# systematic.net
KiCad netlist of a schematic drawn in Altium Designer
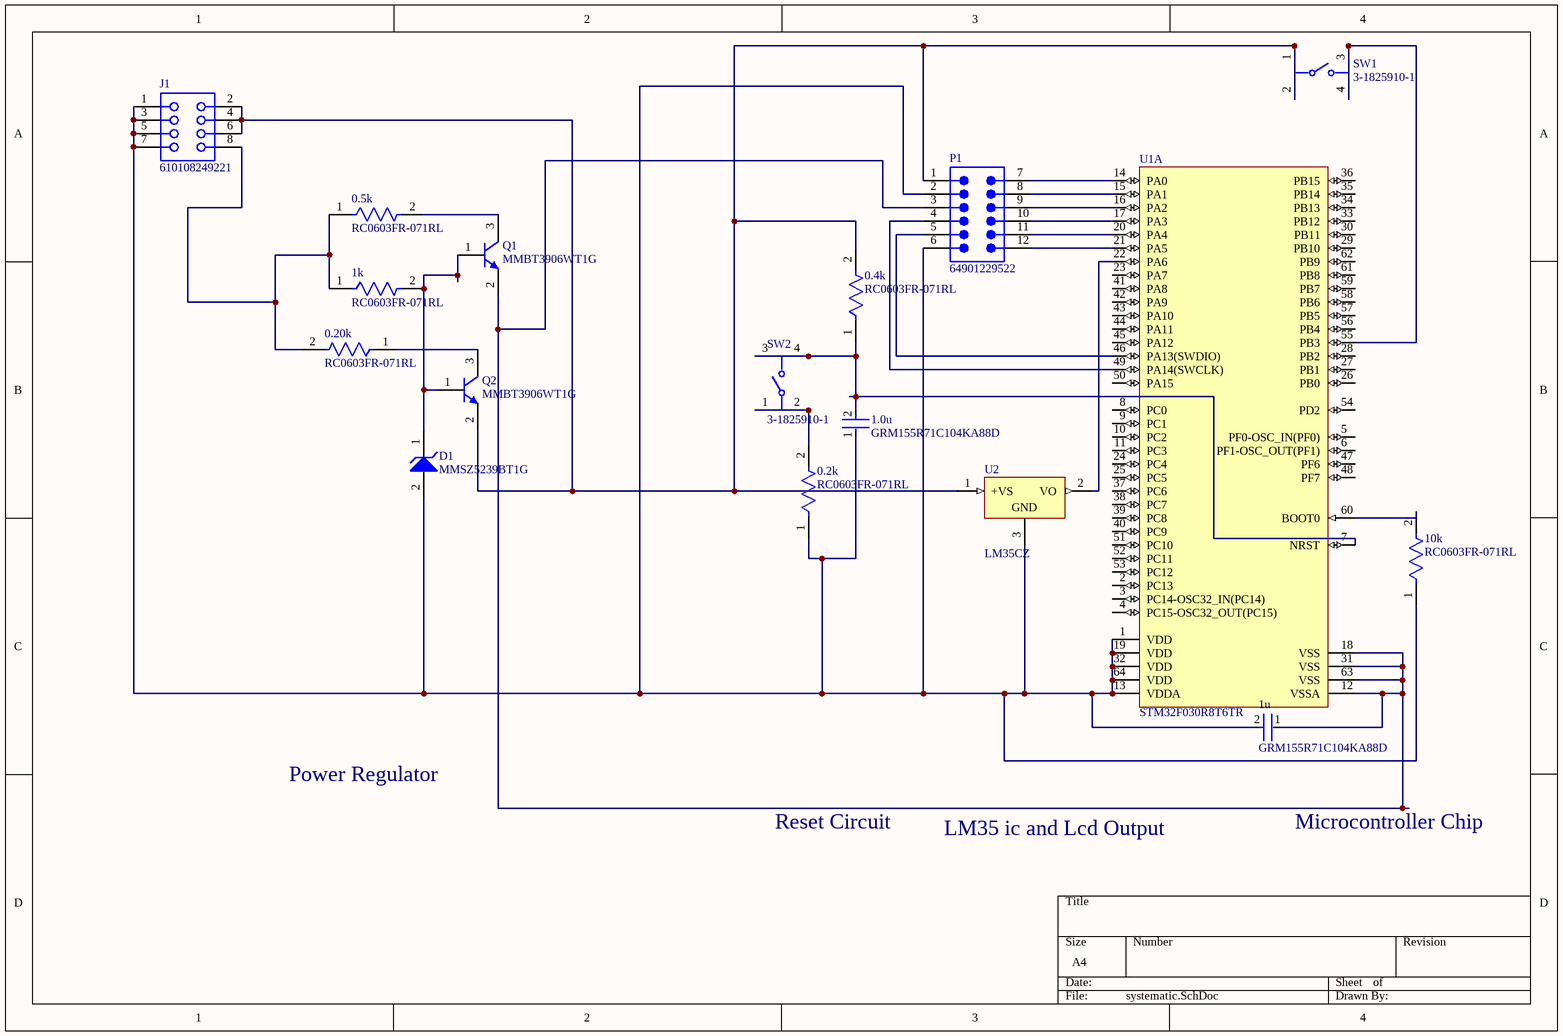
[diagram p0: systematic.SchDoc]

(export (version "E")
  (design (tool "Eeschema 10.0.6"))
  (components
    (comp (ref "0.2k")
      (value "RC0603FR-071RL")
      (footprint "FP-RC0603-0_55-MFG")
      (fields (field (name "TOLERANCE") "1%"))
      (libsource (lib "Altium Content Vault") (part "1029c3af85768c4190bb7ad29bc67b5"))
    )
    (comp (ref "0.4k")
      (value "RC0603FR-071RL")
      (footprint "FP-RC0603-0_55-MFG")
      (fields (field (name "TOLERANCE") "1%"))
      (libsource (lib "Altium Content Vault") (part "1029c3af85768c4190bb7ad29bc67b5"))
    )
    (comp (ref "0.5k")
      (value "RC0603FR-071RL")
      (footprint "FP-RC0603-0_55-MFG")
      (fields (field (name "TOLERANCE") "1%"))
      (libsource (lib "Altium Content Vault") (part "1029c3af85768c4190bb7ad29bc67b5"))
    )
    (comp (ref "0.20k")
      (value "RC0603FR-071RL")
      (footprint "FP-RC0603-0_55-MFG")
      (fields (field (name "TOLERANCE") "1%"))
      (libsource (lib "Altium Content Vault") (part "1029c3af85768c4190bb7ad29bc67b5"))
    )
    (comp (ref "1.0u")
      (value "GRM155R71C104KA88D")
      (footprint "FP-GRM15-MFG")
      (description "CAP CER 0.1UF 16V X7R 0402")
      (fields
        (field (name "TOLERANCE") "10%")
        (field (name "OCTOPART") "https://octopart.com/grm155r71c104ka88d-murata-196880")
      )
      (libsource (lib "Altium Content Vault") (part "236180d848d6139a670b325ea6854c9"))
    )
    (comp (ref "1k")
      (value "RC0603FR-071RL")
      (footprint "FP-RC0603-0_55-MFG")
      (fields (field (name "TOLERANCE") "1%"))
      (libsource (lib "Altium Content Vault") (part "1029c3af85768c4190bb7ad29bc67b5"))
    )
    (comp (ref "1u")
      (value "GRM155R71C104KA88D")
      (footprint "FP-GRM15-MFG")
      (description "CAP CER 0.1UF 16V X7R 0402")
      (fields
        (field (name "TOLERANCE") "10%")
        (field (name "OCTOPART") "https://octopart.com/grm155r71c104ka88d-murata-196880")
      )
      (libsource (lib "Altium Content Vault") (part "236180d848d6139a670b325ea6854c9"))
    )
    (comp (ref "10k")
      (value "RC0603FR-071RL")
      (footprint "FP-RC0603-0_55-MFG")
      (fields (field (name "TOLERANCE") "1%"))
      (libsource (lib "Altium Content Vault") (part "1029c3af85768c4190bb7ad29bc67b5"))
    )
    (comp (ref "D1")
      (value "MMSZ5239BT1G")
      (footprint "ONSC-SOD-123-2-425-04_V")
      (description "Zener Voltage Regulator, 500 mW, 2-Pin SOD-123, Pb-Free, Tape and Reel")
      (fields (field (name "MANUFACTURER") "On Semiconductor"))
      (libsource (lib "Altium Content Vault") (part "ONSC-K1A2-2"))
    )
    (comp (ref "J1")
      (value "610108249221")
      (footprint "610108249221")
      (libsource (lib "Altium Content Vault") (part "Header_Female_2R_08P"))
    )
    (comp (ref "P1")
      (value "64901229522")
      (footprint "64901229522")
      (libsource (lib "Altium Content Vault") (part "Header_Male_2R_12P(A)"))
    )
    (comp (ref "Q1")
      (value "MMBT3906WT1G")
      (footprint "ONSC-SC-70-3-419-04_V")
      (description "General Purpose Transistor, PNP Silicon, 3-Pin SC70, Pb-Free, Tape and Reel")
      (fields (field (name "MANUFACTURER") "On Semiconductor"))
      (libsource (lib "Altium Content Vault") (part "ONSC-NPN-B1E2C3-3"))
    )
    (comp (ref "Q2")
      (value "MMBT3906WT1G")
      (footprint "ONSC-SC-70-3-419-04_V")
      (description "General Purpose Transistor, PNP Silicon, 3-Pin SC70, Pb-Free, Tape and Reel")
      (fields (field (name "MANUFACTURER") "On Semiconductor"))
      (libsource (lib "Altium Content Vault") (part "ONSC-NPN-B1E2C3-3"))
    )
    (comp (ref "SW1")
      (value "3-1825910-1")
      (footprint "FP-3-1825910-1-MFG")
      (description "Switch Tactile OFF (ON) SPST Round Button PC Pins 0.05A 24VDC 100000Cycles 1.57N Thru-Hole")
      (fields (field (name "MANUFACTURER") "TE Connectivity"))
      (libsource (lib "Altium Content Vault") (part "b8895f3f4cefb76e1819d2863dba89b"))
    )
    (comp (ref "SW2")
      (value "3-1825910-1")
      (footprint "FP-3-1825910-1-MFG")
      (description "Switch Tactile OFF (ON) SPST Round Button PC Pins 0.05A 24VDC 100000Cycles 1.57N Thru-Hole")
      (fields (field (name "MANUFACTURER") "TE Connectivity"))
      (libsource (lib "Altium Content Vault") (part "b8895f3f4cefb76e1819d2863dba89b"))
    )
    (comp (ref "U1")
      (value "STM32F030R8T6TR")
      (footprint "STM-LQFP64_L")
      (fields (field (name "MANUFACTURER") "STMicroelectronics"))
      (libsource (lib "Altium Content Vault") (part "STM-STM32F030R8-LQFP64_A"))
    )
    (comp (ref "U2")
      (value "LM35CZ")
      (footprint "Z03A")
      (description "Precision Centigrade Temperature Sensor, 3-pin TO-92")
      (fields (field (name "MANUFACTURER") "National Semiconductor"))
      (libsource (lib "Altium Content Vault") (part "SEN-TEMP-LM34AH-3"))
    )
  )
  (nets
    (net (code "1") (name "Net-(0.2k-Pad2)") (class "Default")
      (node (ref "0.2k") (pin "2") (pinfunction "2_2") (pintype "passive"))
      (node (ref "SW2") (pin "1") (pinfunction "1_1") (pintype "passive"))
      (node (ref "SW2") (pin "2") (pinfunction "2_2") (pintype "passive"))
    )
    (net (code "2") (name "Net-(0.20k-Pad2)") (class "Default")
      (node (ref "0.20k") (pin "2") (pinfunction "2_2") (pintype "passive"))
      (node (ref "0.5k") (pin "1") (pinfunction "1_1") (pintype "passive"))
      (node (ref "1k") (pin "1") (pinfunction "1_1") (pintype "passive"))
      (node (ref "J1") (pin "8") (pinfunction "8_8") (pintype "passive"))
    )
    (net (code "3") (name "Net-(D1-A)") (class "Default")
      (node (ref "0.2k") (pin "1") (pinfunction "1_1") (pintype "passive"))
      (node (ref "1.0u") (pin "1") (pinfunction "1_1") (pintype "passive"))
      (node (ref "10k") (pin "1") (pinfunction "1_1") (pintype "passive"))
      (node (ref "1u") (pin "2") (pinfunction "2_2") (pintype "passive"))
      (node (ref "D1") (pin "2") (pinfunction "A_2") (pintype "passive"))
      (node (ref "J1") (pin "1") (pinfunction "1_1") (pintype "passive"))
      (node (ref "J1") (pin "3") (pinfunction "3_3") (pintype "passive"))
      (node (ref "J1") (pin "5") (pinfunction "5_5") (pintype "passive"))
      (node (ref "J1") (pin "7") (pinfunction "7_7") (pintype "passive"))
      (node (ref "P1") (pin "2") (pinfunction "2_2") (pintype "passive"))
      (node (ref "P1") (pin "6") (pinfunction "6_6") (pintype "passive"))
      (node (ref "U1") (pin "1") (pinfunction "VDD_1") (pintype "power_in"))
      (node (ref "U1") (pin "13") (pinfunction "VDDA_13") (pintype "power_in"))
      (node (ref "U1") (pin "19") (pinfunction "VDD_19") (pintype "power_in"))
      (node (ref "U1") (pin "32") (pinfunction "VDD_32") (pintype "power_in"))
      (node (ref "U1") (pin "64") (pinfunction "VDD_64") (pintype "power_in"))
      (node (ref "U2") (pin "3") (pinfunction "GND_3") (pintype "power_in"))
    )
    (net (code "4") (name "Net-(D1-K)") (class "Default")
      (node (ref "1k") (pin "2") (pinfunction "2_2") (pintype "passive"))
      (node (ref "D1") (pin "1") (pinfunction "K_1") (pintype "passive"))
      (node (ref "Q1") (pin "1") (pinfunction "B_1") (pintype "passive"))
      (node (ref "Q2") (pin "1") (pinfunction "B_1") (pintype "passive"))
    )
    (net (code "5") (name "Net-(Q1-C)") (class "Default")
      (node (ref "0.5k") (pin "2") (pinfunction "2_2") (pintype "passive"))
      (node (ref "Q1") (pin "3") (pinfunction "C_3") (pintype "passive"))
    )
    (net (code "6") (name "Net-(Q1-E)") (class "Default")
      (node (ref "1u") (pin "1") (pinfunction "1_1") (pintype "passive"))
      (node (ref "P1") (pin "3") (pinfunction "3_3") (pintype "passive"))
      (node (ref "Q1") (pin "2") (pinfunction "E_2") (pintype "passive"))
      (node (ref "U1") (pin "12") (pinfunction "VSSA_12") (pintype "power_in"))
      (node (ref "U1") (pin "18") (pinfunction "VSS_18") (pintype "power_in"))
      (node (ref "U1") (pin "31") (pinfunction "VSS_31") (pintype "power_in"))
      (node (ref "U1") (pin "63") (pinfunction "VSS_63") (pintype "power_in"))
    )
    (net (code "7") (name "Net-(Q2-C)") (class "Default")
      (node (ref "0.20k") (pin "1") (pinfunction "1_1") (pintype "passive"))
      (node (ref "Q2") (pin "3") (pinfunction "C_3") (pintype "passive"))
    )
    (net (code "8") (name "Net-(Q2-E)") (class "Default")
      (node (ref "0.4k") (pin "2") (pinfunction "2_2") (pintype "passive"))
      (node (ref "J1") (pin "2") (pinfunction "2_2") (pintype "passive"))
      (node (ref "J1") (pin "4") (pinfunction "4_4") (pintype "passive"))
      (node (ref "J1") (pin "6") (pinfunction "6_6") (pintype "passive"))
      (node (ref "P1") (pin "1") (pinfunction "1_1") (pintype "passive"))
      (node (ref "Q2") (pin "2") (pinfunction "E_2") (pintype "passive"))
      (node (ref "SW1") (pin "1") (pinfunction "1_1") (pintype "passive"))
      (node (ref "SW1") (pin "2") (pinfunction "2_2") (pintype "passive"))
      (node (ref "U2") (pin "1") (pinfunction "+VS_1") (pintype "input"))
    )
    (net (code "9") (name "Net-(U1-BOOT0)") (class "Default")
      (node (ref "10k") (pin "2") (pinfunction "2_2") (pintype "passive"))
      (node (ref "U1") (pin "60") (pinfunction "BOOT0_60") (pintype "input"))
    )
    (net (code "10") (name "Net-(U1-NRST)") (class "Default")
      (node (ref "0.4k") (pin "1") (pinfunction "1_1") (pintype "passive"))
      (node (ref "1.0u") (pin "2") (pinfunction "2_2") (pintype "passive"))
      (node (ref "SW2") (pin "3") (pinfunction "3_3") (pintype "passive"))
      (node (ref "SW2") (pin "4") (pinfunction "4_4") (pintype "passive"))
      (node (ref "U1") (pin "7") (pinfunction "NRST_7") (pintype "bidirectional"))
    )
    (net (code "11") (name "Net-(U1-PA0)") (class "Default")
      (node (ref "P1") (pin "7") (pinfunction "7_7") (pintype "passive"))
      (node (ref "U1") (pin "14") (pinfunction "PA0_14") (pintype "bidirectional"))
    )
    (net (code "12") (name "Net-(U1-PA1)") (class "Default")
      (node (ref "P1") (pin "8") (pinfunction "8_8") (pintype "passive"))
      (node (ref "U1") (pin "15") (pinfunction "PA1_15") (pintype "bidirectional"))
    )
    (net (code "13") (name "Net-(U1-PA2)") (class "Default")
      (node (ref "P1") (pin "9") (pinfunction "9_9") (pintype "passive"))
      (node (ref "U1") (pin "16") (pinfunction "PA2_16") (pintype "bidirectional"))
    )
    (net (code "14") (name "Net-(U1-PA3)") (class "Default")
      (node (ref "P1") (pin "10") (pinfunction "10_10") (pintype "passive"))
      (node (ref "U1") (pin "17") (pinfunction "PA3_17") (pintype "bidirectional"))
    )
    (net (code "15") (name "Net-(U1-PA4)") (class "Default")
      (node (ref "P1") (pin "11") (pinfunction "11_11") (pintype "passive"))
      (node (ref "U1") (pin "20") (pinfunction "PA4_20") (pintype "bidirectional"))
    )
    (net (code "16") (name "Net-(U1-PA5)") (class "Default")
      (node (ref "P1") (pin "12") (pinfunction "12_12") (pintype "passive"))
      (node (ref "U1") (pin "21") (pinfunction "PA5_21") (pintype "bidirectional"))
    )
    (net (code "17") (name "Net-(U1-PA6)") (class "Default")
      (node (ref "U1") (pin "22") (pinfunction "PA6_22") (pintype "bidirectional"))
      (node (ref "U2") (pin "2") (pinfunction "VO_2") (pintype "output"))
    )
    (net (code "18") (name "Net-(U1-PA13(SWDIO))") (class "Default")
      (node (ref "P1") (pin "5") (pinfunction "5_5") (pintype "passive"))
      (node (ref "U1") (pin "46") (pinfunction "PA13(SWDIO)_46") (pintype "bidirectional"))
    )
    (net (code "19") (name "Net-(U1-PA14(SWCLK))") (class "Default")
      (node (ref "P1") (pin "4") (pinfunction "4_4") (pintype "passive"))
      (node (ref "U1") (pin "49") (pinfunction "PA14(SWCLK)_49") (pintype "bidirectional"))
    )
    (net (code "20") (name "Net-(U1-PB3)") (class "Default")
      (node (ref "SW1") (pin "3") (pinfunction "3_3") (pintype "passive"))
      (node (ref "SW1") (pin "4") (pinfunction "4_4") (pintype "passive"))
      (node (ref "U1") (pin "55") (pinfunction "PB3_55") (pintype "bidirectional"))
    )
    (net (code "21") (name "unconnected-(U1-PA7-Pad23)") (class "Default")
      (node (ref "U1") (pin "23") (pinfunction "PA7_23") (pintype "bidirectional"))
    )
    (net (code "22") (name "unconnected-(U1-PA8-Pad41)") (class "Default")
      (node (ref "U1") (pin "41") (pinfunction "PA8_41") (pintype "bidirectional"))
    )
    (net (code "23") (name "unconnected-(U1-PA9-Pad42)") (class "Default")
      (node (ref "U1") (pin "42") (pinfunction "PA9_42") (pintype "bidirectional"))
    )
    (net (code "24") (name "unconnected-(U1-PA10-Pad43)") (class "Default")
      (node (ref "U1") (pin "43") (pinfunction "PA10_43") (pintype "bidirectional"))
    )
    (net (code "25") (name "unconnected-(U1-PA11-Pad44)") (class "Default")
      (node (ref "U1") (pin "44") (pinfunction "PA11_44") (pintype "bidirectional"))
    )
    (net (code "26") (name "unconnected-(U1-PA12-Pad45)") (class "Default")
      (node (ref "U1") (pin "45") (pinfunction "PA12_45") (pintype "bidirectional"))
    )
    (net (code "27") (name "unconnected-(U1-PA15-Pad50)") (class "Default")
      (node (ref "U1") (pin "50") (pinfunction "PA15_50") (pintype "bidirectional"))
    )
    (net (code "28") (name "unconnected-(U1-PB0-Pad26)") (class "Default")
      (node (ref "U1") (pin "26") (pinfunction "PB0_26") (pintype "bidirectional"))
    )
    (net (code "29") (name "unconnected-(U1-PB1-Pad27)") (class "Default")
      (node (ref "U1") (pin "27") (pinfunction "PB1_27") (pintype "bidirectional"))
    )
    (net (code "30") (name "unconnected-(U1-PB2-Pad28)") (class "Default")
      (node (ref "U1") (pin "28") (pinfunction "PB2_28") (pintype "bidirectional"))
    )
    (net (code "31") (name "unconnected-(U1-PB4-Pad56)") (class "Default")
      (node (ref "U1") (pin "56") (pinfunction "PB4_56") (pintype "bidirectional"))
    )
    (net (code "32") (name "unconnected-(U1-PB5-Pad57)") (class "Default")
      (node (ref "U1") (pin "57") (pinfunction "PB5_57") (pintype "bidirectional"))
    )
    (net (code "33") (name "unconnected-(U1-PB6-Pad58)") (class "Default")
      (node (ref "U1") (pin "58") (pinfunction "PB6_58") (pintype "bidirectional"))
    )
    (net (code "34") (name "unconnected-(U1-PB7-Pad59)") (class "Default")
      (node (ref "U1") (pin "59") (pinfunction "PB7_59") (pintype "bidirectional"))
    )
    (net (code "35") (name "unconnected-(U1-PB8-Pad61)") (class "Default")
      (node (ref "U1") (pin "61") (pinfunction "PB8_61") (pintype "bidirectional"))
    )
    (net (code "36") (name "unconnected-(U1-PB9-Pad62)") (class "Default")
      (node (ref "U1") (pin "62") (pinfunction "PB9_62") (pintype "bidirectional"))
    )
    (net (code "37") (name "unconnected-(U1-PB10-Pad29)") (class "Default")
      (node (ref "U1") (pin "29") (pinfunction "PB10_29") (pintype "bidirectional"))
    )
    (net (code "38") (name "unconnected-(U1-PB11-Pad30)") (class "Default")
      (node (ref "U1") (pin "30") (pinfunction "PB11_30") (pintype "bidirectional"))
    )
    (net (code "39") (name "unconnected-(U1-PB12-Pad33)") (class "Default")
      (node (ref "U1") (pin "33") (pinfunction "PB12_33") (pintype "bidirectional"))
    )
    (net (code "40") (name "unconnected-(U1-PB13-Pad34)") (class "Default")
      (node (ref "U1") (pin "34") (pinfunction "PB13_34") (pintype "bidirectional"))
    )
    (net (code "41") (name "unconnected-(U1-PB14-Pad35)") (class "Default")
      (node (ref "U1") (pin "35") (pinfunction "PB14_35") (pintype "bidirectional"))
    )
    (net (code "42") (name "unconnected-(U1-PB15-Pad36)") (class "Default")
      (node (ref "U1") (pin "36") (pinfunction "PB15_36") (pintype "bidirectional"))
    )
    (net (code "43") (name "unconnected-(U1-PC0-Pad8)") (class "Default")
      (node (ref "U1") (pin "8") (pinfunction "PC0_8") (pintype "bidirectional"))
    )
    (net (code "44") (name "unconnected-(U1-PC1-Pad9)") (class "Default")
      (node (ref "U1") (pin "9") (pinfunction "PC1_9") (pintype "bidirectional"))
    )
    (net (code "45") (name "unconnected-(U1-PC2-Pad10)") (class "Default")
      (node (ref "U1") (pin "10") (pinfunction "PC2_10") (pintype "bidirectional"))
    )
    (net (code "46") (name "unconnected-(U1-PC3-Pad11)") (class "Default")
      (node (ref "U1") (pin "11") (pinfunction "PC3_11") (pintype "bidirectional"))
    )
    (net (code "47") (name "unconnected-(U1-PC4-Pad24)") (class "Default")
      (node (ref "U1") (pin "24") (pinfunction "PC4_24") (pintype "bidirectional"))
    )
    (net (code "48") (name "unconnected-(U1-PC5-Pad25)") (class "Default")
      (node (ref "U1") (pin "25") (pinfunction "PC5_25") (pintype "bidirectional"))
    )
    (net (code "49") (name "unconnected-(U1-PC6-Pad37)") (class "Default")
      (node (ref "U1") (pin "37") (pinfunction "PC6_37") (pintype "bidirectional"))
    )
    (net (code "50") (name "unconnected-(U1-PC7-Pad38)") (class "Default")
      (node (ref "U1") (pin "38") (pinfunction "PC7_38") (pintype "bidirectional"))
    )
    (net (code "51") (name "unconnected-(U1-PC8-Pad39)") (class "Default")
      (node (ref "U1") (pin "39") (pinfunction "PC8_39") (pintype "bidirectional"))
    )
    (net (code "52") (name "unconnected-(U1-PC9-Pad40)") (class "Default")
      (node (ref "U1") (pin "40") (pinfunction "PC9_40") (pintype "bidirectional"))
    )
    (net (code "53") (name "unconnected-(U1-PC10-Pad51)") (class "Default")
      (node (ref "U1") (pin "51") (pinfunction "PC10_51") (pintype "bidirectional"))
    )
    (net (code "54") (name "unconnected-(U1-PC11-Pad52)") (class "Default")
      (node (ref "U1") (pin "52") (pinfunction "PC11_52") (pintype "bidirectional"))
    )
    (net (code "55") (name "unconnected-(U1-PC12-Pad53)") (class "Default")
      (node (ref "U1") (pin "53") (pinfunction "PC12_53") (pintype "bidirectional"))
    )
    (net (code "56") (name "unconnected-(U1-PC13-Pad2)") (class "Default")
      (node (ref "U1") (pin "2") (pinfunction "PC13_2") (pintype "bidirectional"))
    )
    (net (code "57") (name "unconnected-(U1-PC14-OSC32_IN(PC14)-Pad3)") (class "Default")
      (node (ref "U1") (pin "3") (pinfunction "PC14-OSC32_IN(PC14)_3") (pintype "bidirectional"))
    )
    (net (code "58") (name "unconnected-(U1-PC15-OSC32_OUT(PC15)-Pad4)") (class "Default")
      (node (ref "U1") (pin "4") (pinfunction "PC15-OSC32_OUT(PC15)_4") (pintype "bidirectional"))
    )
    (net (code "59") (name "unconnected-(U1-PD2-Pad54)") (class "Default")
      (node (ref "U1") (pin "54") (pinfunction "PD2_54") (pintype "bidirectional"))
    )
    (net (code "60") (name "unconnected-(U1-PF0-OSC_IN(PF0)-Pad5)") (class "Default")
      (node (ref "U1") (pin "5") (pinfunction "PF0-OSC_IN(PF0)_5") (pintype "bidirectional"))
    )
    (net (code "61") (name "unconnected-(U1-PF1-OSC_OUT(PF1)-Pad6)") (class "Default")
      (node (ref "U1") (pin "6") (pinfunction "PF1-OSC_OUT(PF1)_6") (pintype "bidirectional"))
    )
    (net (code "62") (name "unconnected-(U1-PF6-Pad47)") (class "Default")
      (node (ref "U1") (pin "47") (pinfunction "PF6_47") (pintype "bidirectional"))
    )
    (net (code "63") (name "unconnected-(U1-PF7-Pad48)") (class "Default")
      (node (ref "U1") (pin "48") (pinfunction "PF7_48") (pintype "bidirectional"))
    )
  )
)
